# SJA1105Q_PINOUT.net
KiCad netlist of a schematic drawn in Altium Designer
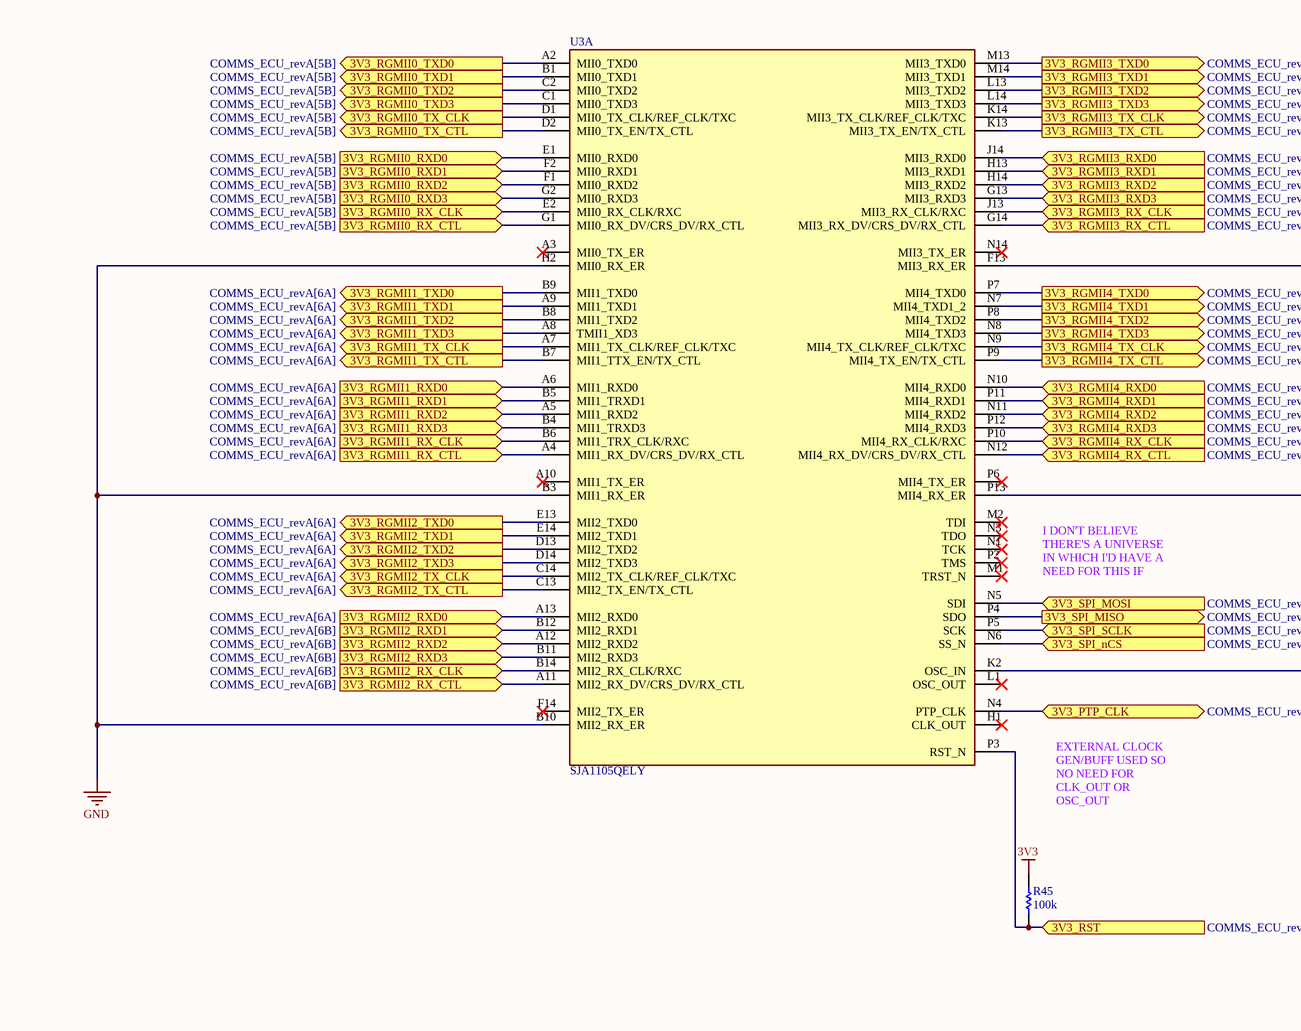
[diagram p0: SJA1105Q_PINOUT.SchDoc, top left]
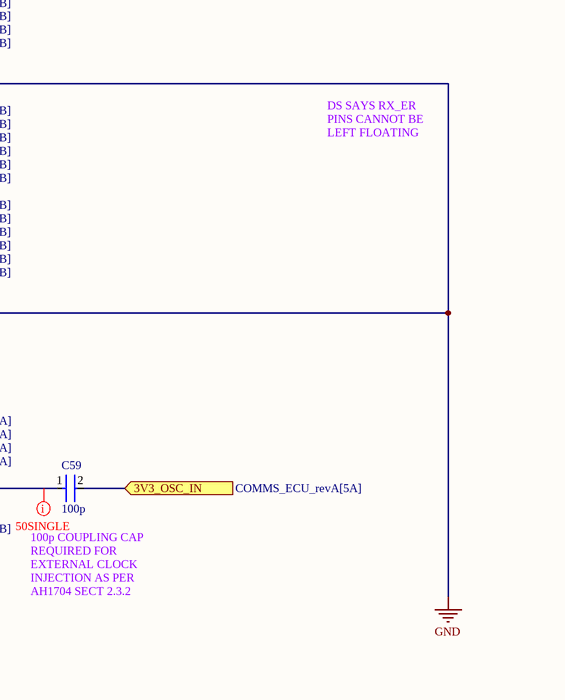
[diagram p1: SJA1105Q_PINOUT.SchDoc, top right]
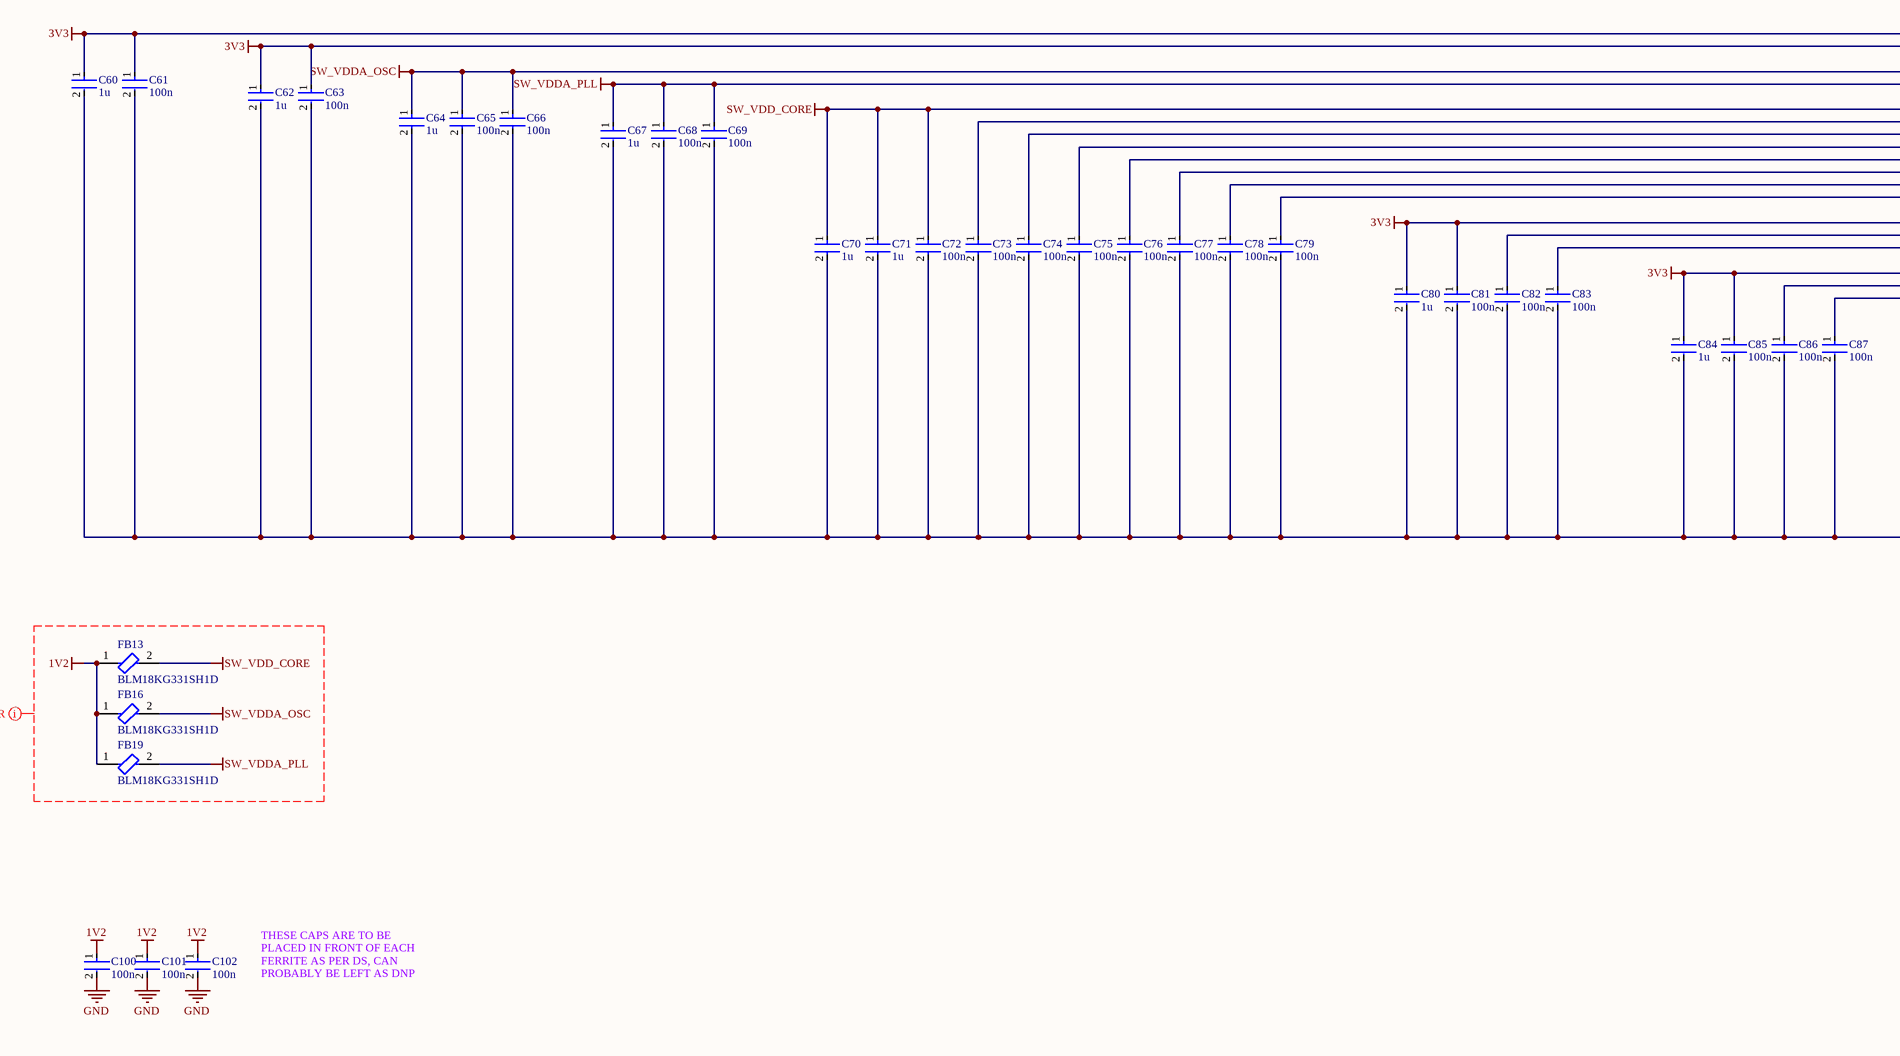
[diagram p2: SJA1105Q_PINOUT.SchDoc, bottom left]
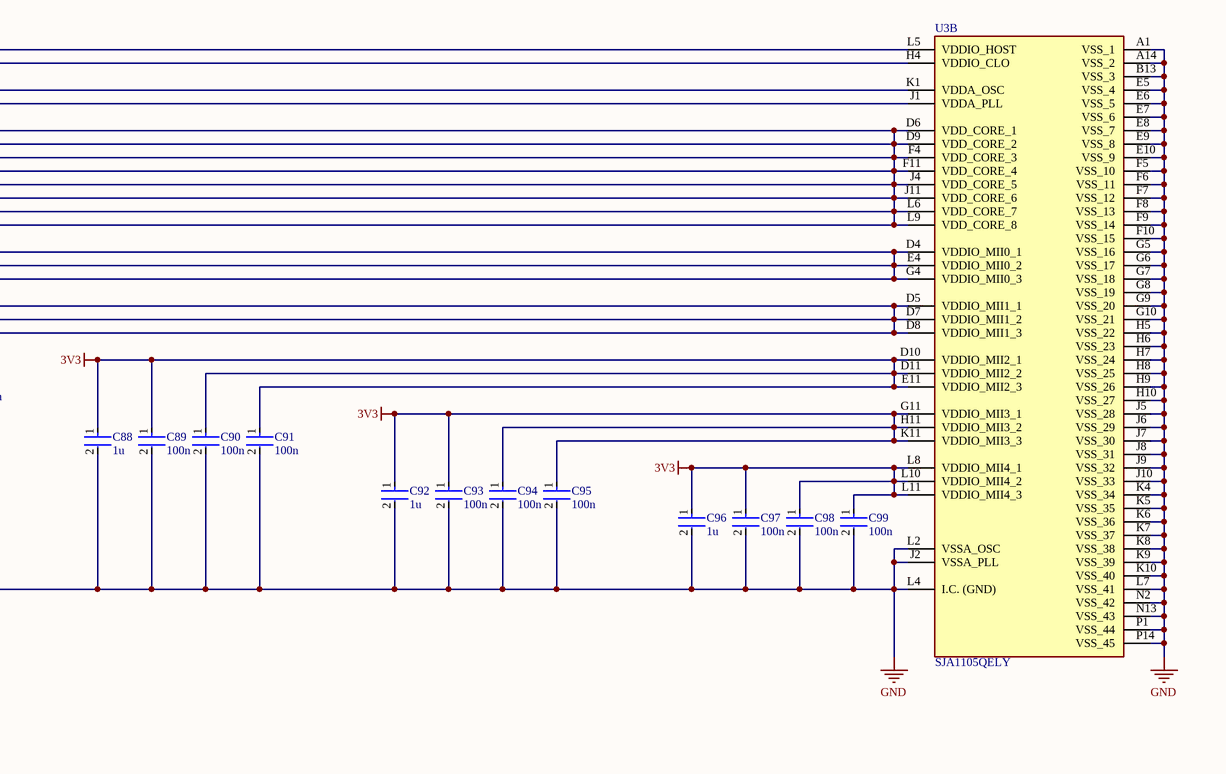
[diagram p3: SJA1105Q_PINOUT.SchDoc, bottom right]

(export (version "E")
  (design (tool "Eeschema 10.0.6"))
  (components
    (comp (ref "C59")
      (value "100p")
      (footprint "FP-0402-L_1_0_0_05-W_0_5-IPC_A")
      (description "LARGE PADS, 0402 CAP, CHANGE COMMENT TO MATCH REAL P/N")
      (libsource (lib "Space Concordia") (part "b4654b650e69147ec39a6b967a45e02"))
    )
    (comp (ref "C60")
      (value "1u")
      (footprint "FP-0402-L_1_0_0_05-W_0_5-IPC_A")
      (description "LARGE PADS, 0402 CAP, CHANGE COMMENT TO MATCH REAL P/N")
      (libsource (lib "Space Concordia") (part "b4654b650e69147ec39a6b967a45e02"))
    )
    (comp (ref "C61")
      (value "100n")
      (footprint "FP-0402-L_1_0_0_05-W_0_5-IPC_A")
      (description "LARGE PADS, 0402 CAP, CHANGE COMMENT TO MATCH REAL P/N")
      (libsource (lib "Space Concordia") (part "b4654b650e69147ec39a6b967a45e02"))
    )
    (comp (ref "C62")
      (value "1u")
      (footprint "FP-0402-L_1_0_0_05-W_0_5-IPC_A")
      (description "LARGE PADS, 0402 CAP, CHANGE COMMENT TO MATCH REAL P/N")
      (libsource (lib "Space Concordia") (part "b4654b650e69147ec39a6b967a45e02"))
    )
    (comp (ref "C63")
      (value "100n")
      (footprint "FP-0402-L_1_0_0_05-W_0_5-IPC_A")
      (description "LARGE PADS, 0402 CAP, CHANGE COMMENT TO MATCH REAL P/N")
      (libsource (lib "Space Concordia") (part "b4654b650e69147ec39a6b967a45e02"))
    )
    (comp (ref "C64")
      (value "1u")
      (footprint "FP-0402-L_1_0_0_05-W_0_5-IPC_A")
      (description "LARGE PADS, 0402 CAP, CHANGE COMMENT TO MATCH REAL P/N")
      (libsource (lib "Space Concordia") (part "b4654b650e69147ec39a6b967a45e02"))
    )
    (comp (ref "C65")
      (value "100n")
      (footprint "FP-0402-L_1_0_0_05-W_0_5-IPC_A")
      (description "LARGE PADS, 0402 CAP, CHANGE COMMENT TO MATCH REAL P/N")
      (libsource (lib "Space Concordia") (part "b4654b650e69147ec39a6b967a45e02"))
    )
    (comp (ref "C66")
      (value "100n")
      (footprint "FP-0402-L_1_0_0_05-W_0_5-IPC_A")
      (description "LARGE PADS, 0402 CAP, CHANGE COMMENT TO MATCH REAL P/N")
      (libsource (lib "Space Concordia") (part "b4654b650e69147ec39a6b967a45e02"))
    )
    (comp (ref "C67")
      (value "1u")
      (footprint "FP-0402-L_1_0_0_05-W_0_5-IPC_A")
      (description "LARGE PADS, 0402 CAP, CHANGE COMMENT TO MATCH REAL P/N")
      (libsource (lib "Space Concordia") (part "b4654b650e69147ec39a6b967a45e02"))
    )
    (comp (ref "C68")
      (value "100n")
      (footprint "FP-0402-L_1_0_0_05-W_0_5-IPC_A")
      (description "LARGE PADS, 0402 CAP, CHANGE COMMENT TO MATCH REAL P/N")
      (libsource (lib "Space Concordia") (part "b4654b650e69147ec39a6b967a45e02"))
    )
    (comp (ref "C69")
      (value "100n")
      (footprint "FP-0402-L_1_0_0_05-W_0_5-IPC_A")
      (description "LARGE PADS, 0402 CAP, CHANGE COMMENT TO MATCH REAL P/N")
      (libsource (lib "Space Concordia") (part "b4654b650e69147ec39a6b967a45e02"))
    )
    (comp (ref "C70")
      (value "1u")
      (footprint "FP-0402-L_1_0_0_05-W_0_5-IPC_A")
      (description "LARGE PADS, 0402 CAP, CHANGE COMMENT TO MATCH REAL P/N")
      (libsource (lib "Space Concordia") (part "b4654b650e69147ec39a6b967a45e02"))
    )
    (comp (ref "C71")
      (value "1u")
      (footprint "FP-0402-L_1_0_0_05-W_0_5-IPC_A")
      (description "LARGE PADS, 0402 CAP, CHANGE COMMENT TO MATCH REAL P/N")
      (libsource (lib "Space Concordia") (part "b4654b650e69147ec39a6b967a45e02"))
    )
    (comp (ref "C72")
      (value "100n")
      (footprint "FP-0402-L_1_0_0_05-W_0_5-IPC_A")
      (description "LARGE PADS, 0402 CAP, CHANGE COMMENT TO MATCH REAL P/N")
      (libsource (lib "Space Concordia") (part "b4654b650e69147ec39a6b967a45e02"))
    )
    (comp (ref "C73")
      (value "100n")
      (footprint "FP-0402-L_1_0_0_05-W_0_5-IPC_A")
      (description "LARGE PADS, 0402 CAP, CHANGE COMMENT TO MATCH REAL P/N")
      (libsource (lib "Space Concordia") (part "b4654b650e69147ec39a6b967a45e02"))
    )
    (comp (ref "C74")
      (value "100n")
      (footprint "FP-0402-L_1_0_0_05-W_0_5-IPC_A")
      (description "LARGE PADS, 0402 CAP, CHANGE COMMENT TO MATCH REAL P/N")
      (libsource (lib "Space Concordia") (part "b4654b650e69147ec39a6b967a45e02"))
    )
    (comp (ref "C75")
      (value "100n")
      (footprint "FP-0402-L_1_0_0_05-W_0_5-IPC_A")
      (description "LARGE PADS, 0402 CAP, CHANGE COMMENT TO MATCH REAL P/N")
      (libsource (lib "Space Concordia") (part "b4654b650e69147ec39a6b967a45e02"))
    )
    (comp (ref "C76")
      (value "100n")
      (footprint "FP-0402-L_1_0_0_05-W_0_5-IPC_A")
      (description "LARGE PADS, 0402 CAP, CHANGE COMMENT TO MATCH REAL P/N")
      (libsource (lib "Space Concordia") (part "b4654b650e69147ec39a6b967a45e02"))
    )
    (comp (ref "C77")
      (value "100n")
      (footprint "FP-0402-L_1_0_0_05-W_0_5-IPC_A")
      (description "LARGE PADS, 0402 CAP, CHANGE COMMENT TO MATCH REAL P/N")
      (libsource (lib "Space Concordia") (part "b4654b650e69147ec39a6b967a45e02"))
    )
    (comp (ref "C78")
      (value "100n")
      (footprint "FP-0402-L_1_0_0_05-W_0_5-IPC_A")
      (description "LARGE PADS, 0402 CAP, CHANGE COMMENT TO MATCH REAL P/N")
      (libsource (lib "Space Concordia") (part "b4654b650e69147ec39a6b967a45e02"))
    )
    (comp (ref "C79")
      (value "100n")
      (footprint "FP-0402-L_1_0_0_05-W_0_5-IPC_A")
      (description "LARGE PADS, 0402 CAP, CHANGE COMMENT TO MATCH REAL P/N")
      (libsource (lib "Space Concordia") (part "b4654b650e69147ec39a6b967a45e02"))
    )
    (comp (ref "C80")
      (value "1u")
      (footprint "FP-0402-L_1_0_0_05-W_0_5-IPC_A")
      (description "LARGE PADS, 0402 CAP, CHANGE COMMENT TO MATCH REAL P/N")
      (libsource (lib "Space Concordia") (part "b4654b650e69147ec39a6b967a45e02"))
    )
    (comp (ref "C81")
      (value "100n")
      (footprint "FP-0402-L_1_0_0_05-W_0_5-IPC_A")
      (description "LARGE PADS, 0402 CAP, CHANGE COMMENT TO MATCH REAL P/N")
      (libsource (lib "Space Concordia") (part "b4654b650e69147ec39a6b967a45e02"))
    )
    (comp (ref "C82")
      (value "100n")
      (footprint "FP-0402-L_1_0_0_05-W_0_5-IPC_A")
      (description "LARGE PADS, 0402 CAP, CHANGE COMMENT TO MATCH REAL P/N")
      (libsource (lib "Space Concordia") (part "b4654b650e69147ec39a6b967a45e02"))
    )
    (comp (ref "C83")
      (value "100n")
      (footprint "FP-0402-L_1_0_0_05-W_0_5-IPC_A")
      (description "LARGE PADS, 0402 CAP, CHANGE COMMENT TO MATCH REAL P/N")
      (libsource (lib "Space Concordia") (part "b4654b650e69147ec39a6b967a45e02"))
    )
    (comp (ref "C84")
      (value "1u")
      (footprint "FP-0402-L_1_0_0_05-W_0_5-IPC_A")
      (description "LARGE PADS, 0402 CAP, CHANGE COMMENT TO MATCH REAL P/N")
      (libsource (lib "Space Concordia") (part "b4654b650e69147ec39a6b967a45e02"))
    )
    (comp (ref "C85")
      (value "100n")
      (footprint "FP-0402-L_1_0_0_05-W_0_5-IPC_A")
      (description "LARGE PADS, 0402 CAP, CHANGE COMMENT TO MATCH REAL P/N")
      (libsource (lib "Space Concordia") (part "b4654b650e69147ec39a6b967a45e02"))
    )
    (comp (ref "C86")
      (value "100n")
      (footprint "FP-0402-L_1_0_0_05-W_0_5-IPC_A")
      (description "LARGE PADS, 0402 CAP, CHANGE COMMENT TO MATCH REAL P/N")
      (libsource (lib "Space Concordia") (part "b4654b650e69147ec39a6b967a45e02"))
    )
    (comp (ref "C87")
      (value "100n")
      (footprint "FP-0402-L_1_0_0_05-W_0_5-IPC_A")
      (description "LARGE PADS, 0402 CAP, CHANGE COMMENT TO MATCH REAL P/N")
      (libsource (lib "Space Concordia") (part "b4654b650e69147ec39a6b967a45e02"))
    )
    (comp (ref "C88")
      (value "1u")
      (footprint "FP-0402-L_1_0_0_05-W_0_5-IPC_A")
      (description "LARGE PADS, 0402 CAP, CHANGE COMMENT TO MATCH REAL P/N")
      (libsource (lib "Space Concordia") (part "b4654b650e69147ec39a6b967a45e02"))
    )
    (comp (ref "C89")
      (value "100n")
      (footprint "FP-0402-L_1_0_0_05-W_0_5-IPC_A")
      (description "LARGE PADS, 0402 CAP, CHANGE COMMENT TO MATCH REAL P/N")
      (libsource (lib "Space Concordia") (part "b4654b650e69147ec39a6b967a45e02"))
    )
    (comp (ref "C90")
      (value "100n")
      (footprint "FP-0402-L_1_0_0_05-W_0_5-IPC_A")
      (description "LARGE PADS, 0402 CAP, CHANGE COMMENT TO MATCH REAL P/N")
      (libsource (lib "Space Concordia") (part "b4654b650e69147ec39a6b967a45e02"))
    )
    (comp (ref "C91")
      (value "100n")
      (footprint "FP-0402-L_1_0_0_05-W_0_5-IPC_A")
      (description "LARGE PADS, 0402 CAP, CHANGE COMMENT TO MATCH REAL P/N")
      (libsource (lib "Space Concordia") (part "b4654b650e69147ec39a6b967a45e02"))
    )
    (comp (ref "C92")
      (value "1u")
      (footprint "FP-0402-L_1_0_0_05-W_0_5-IPC_A")
      (description "LARGE PADS, 0402 CAP, CHANGE COMMENT TO MATCH REAL P/N")
      (libsource (lib "Space Concordia") (part "b4654b650e69147ec39a6b967a45e02"))
    )
    (comp (ref "C93")
      (value "100n")
      (footprint "FP-0402-L_1_0_0_05-W_0_5-IPC_A")
      (description "LARGE PADS, 0402 CAP, CHANGE COMMENT TO MATCH REAL P/N")
      (libsource (lib "Space Concordia") (part "b4654b650e69147ec39a6b967a45e02"))
    )
    (comp (ref "C94")
      (value "100n")
      (footprint "FP-0402-L_1_0_0_05-W_0_5-IPC_A")
      (description "LARGE PADS, 0402 CAP, CHANGE COMMENT TO MATCH REAL P/N")
      (libsource (lib "Space Concordia") (part "b4654b650e69147ec39a6b967a45e02"))
    )
    (comp (ref "C95")
      (value "100n")
      (footprint "FP-0402-L_1_0_0_05-W_0_5-IPC_A")
      (description "LARGE PADS, 0402 CAP, CHANGE COMMENT TO MATCH REAL P/N")
      (libsource (lib "Space Concordia") (part "b4654b650e69147ec39a6b967a45e02"))
    )
    (comp (ref "C96")
      (value "1u")
      (footprint "FP-0402-L_1_0_0_05-W_0_5-IPC_A")
      (description "LARGE PADS, 0402 CAP, CHANGE COMMENT TO MATCH REAL P/N")
      (libsource (lib "Space Concordia") (part "b4654b650e69147ec39a6b967a45e02"))
    )
    (comp (ref "C97")
      (value "100n")
      (footprint "FP-0402-L_1_0_0_05-W_0_5-IPC_A")
      (description "LARGE PADS, 0402 CAP, CHANGE COMMENT TO MATCH REAL P/N")
      (libsource (lib "Space Concordia") (part "b4654b650e69147ec39a6b967a45e02"))
    )
    (comp (ref "C98")
      (value "100n")
      (footprint "FP-0402-L_1_0_0_05-W_0_5-IPC_A")
      (description "LARGE PADS, 0402 CAP, CHANGE COMMENT TO MATCH REAL P/N")
      (libsource (lib "Space Concordia") (part "b4654b650e69147ec39a6b967a45e02"))
    )
    (comp (ref "C99")
      (value "100n")
      (footprint "FP-0402-L_1_0_0_05-W_0_5-IPC_A")
      (description "LARGE PADS, 0402 CAP, CHANGE COMMENT TO MATCH REAL P/N")
      (libsource (lib "Space Concordia") (part "b4654b650e69147ec39a6b967a45e02"))
    )
    (comp (ref "C100")
      (value "100n")
      (footprint "FP-0402-L_1_0_0_05-W_0_5-IPC_A")
      (description "LARGE PADS, 0402 CAP, CHANGE COMMENT TO MATCH REAL P/N")
      (libsource (lib "Space Concordia") (part "b4654b650e69147ec39a6b967a45e02"))
    )
    (comp (ref "C101")
      (value "100n")
      (footprint "FP-0402-L_1_0_0_05-W_0_5-IPC_A")
      (description "LARGE PADS, 0402 CAP, CHANGE COMMENT TO MATCH REAL P/N")
      (libsource (lib "Space Concordia") (part "b4654b650e69147ec39a6b967a45e02"))
    )
    (comp (ref "C102")
      (value "100n")
      (footprint "FP-0402-L_1_0_0_05-W_0_5-IPC_A")
      (description "LARGE PADS, 0402 CAP, CHANGE COMMENT TO MATCH REAL P/N")
      (libsource (lib "Space Concordia") (part "b4654b650e69147ec39a6b967a45e02"))
    )
    (comp (ref "FB13")
      (value "BLM18KG331SH1D")
      (footprint "FP-BLM18-0_15-t0_8-IPC_B")
      (description "Chip Ferrite Bead, 0603, 330Ω @ 100MHz, 0.08Ω, 25%, 1.7A")
      (libsource (lib "Altium Content Vault") (part "5f30dd21d616792df468990f7003faa"))
    )
    (comp (ref "FB16")
      (value "BLM18KG331SH1D")
      (footprint "FP-BLM18-0_15-t0_8-IPC_B")
      (description "Chip Ferrite Bead, 0603, 330Ω @ 100MHz, 0.08Ω, 25%, 1.7A")
      (libsource (lib "Altium Content Vault") (part "5f30dd21d616792df468990f7003faa"))
    )
    (comp (ref "FB19")
      (value "BLM18KG331SH1D")
      (footprint "FP-BLM18-0_15-t0_8-IPC_B")
      (description "Chip Ferrite Bead, 0603, 330Ω @ 100MHz, 0.08Ω, 25%, 1.7A")
      (libsource (lib "Altium Content Vault") (part "5f30dd21d616792df468990f7003faa"))
    )
    (comp (ref "R45")
      (value "100k")
      (footprint "R0603B")
      (description "Resistor")
      (libsource (lib "Space Concordia") (part "Resistor"))
    )
    (comp (ref "U3")
      (value "SJA1105QELY")
      (footprint "SJA1105QELY-Footprint-1")
      (description "Ethernet Controller, Ethernet Switch, IEEE 802.3, 1.2 V, LFBGA, 159 Pins")
      (libsource (lib "Space Concordia") (part "SJA1105QELY"))
    )
  )
  (nets
    (net (code "1") (name "/3V3_OSC_IN") (class "Default")
      (node (ref "C59") (pin "2") (pinfunction "2_2") (pintype "passive"))
    )
    (net (code "2") (name "/3V3_PTP_CLK") (class "Default")
      (node (ref "U3") (pin "N4") (pinfunction "PTP_CLK_N4") (pintype "passive"))
    )
    (net (code "3") (name "/3V3_RGMII0_RXD0") (class "Default")
      (node (ref "U3") (pin "E1") (pinfunction "MII0_RXD0_E1") (pintype "passive"))
    )
    (net (code "4") (name "/3V3_RGMII0_RXD1") (class "Default")
      (node (ref "U3") (pin "F2") (pinfunction "MII0_RXD1_F2") (pintype "passive"))
    )
    (net (code "5") (name "/3V3_RGMII0_RXD2") (class "Default")
      (node (ref "U3") (pin "F1") (pinfunction "MII0_RXD2_F1") (pintype "passive"))
    )
    (net (code "6") (name "/3V3_RGMII0_RXD3") (class "Default")
      (node (ref "U3") (pin "G2") (pinfunction "MII0_RXD3_G2") (pintype "passive"))
    )
    (net (code "7") (name "/3V3_RGMII0_RX_CLK") (class "Default")
      (node (ref "U3") (pin "E2") (pinfunction "MII0_RX_CLK/RXC_E2") (pintype "passive"))
    )
    (net (code "8") (name "/3V3_RGMII0_RX_CTL") (class "Default")
      (node (ref "U3") (pin "G1") (pinfunction "MII0_RX_DV/CRS_DV/RX_CTL_G1") (pintype "passive"))
    )
    (net (code "9") (name "/3V3_RGMII0_TXD0") (class "Default")
      (node (ref "U3") (pin "A2") (pinfunction "MII0_TXD0_A2") (pintype "passive"))
    )
    (net (code "10") (name "/3V3_RGMII0_TXD1") (class "Default")
      (node (ref "U3") (pin "B1") (pinfunction "MII0_TXD1_B1") (pintype "passive"))
    )
    (net (code "11") (name "/3V3_RGMII0_TXD2") (class "Default")
      (node (ref "U3") (pin "C2") (pinfunction "MII0_TXD2_C2") (pintype "passive"))
    )
    (net (code "12") (name "/3V3_RGMII0_TXD3") (class "Default")
      (node (ref "U3") (pin "C1") (pinfunction "MII0_TXD3_C1") (pintype "passive"))
    )
    (net (code "13") (name "/3V3_RGMII0_TX_CLK") (class "Default")
      (node (ref "U3") (pin "D1") (pinfunction "MII0_TX_CLK/REF_CLK/TXC_D1") (pintype "passive"))
    )
    (net (code "14") (name "/3V3_RGMII0_TX_CTL") (class "Default")
      (node (ref "U3") (pin "D2") (pinfunction "MII0_TX_EN/TX_CTL_D2") (pintype "passive"))
    )
    (net (code "15") (name "/3V3_RGMII1_RXD0") (class "Default")
      (node (ref "U3") (pin "A6") (pinfunction "MII1_RXD0_A6") (pintype "passive"))
    )
    (net (code "16") (name "/3V3_RGMII1_RXD1") (class "Default")
      (node (ref "U3") (pin "B5") (pinfunction "MII1_TRXD1_B5") (pintype "passive"))
    )
    (net (code "17") (name "/3V3_RGMII1_RXD2") (class "Default")
      (node (ref "U3") (pin "A5") (pinfunction "MII1_RXD2_A5") (pintype "passive"))
    )
    (net (code "18") (name "/3V3_RGMII1_RXD3") (class "Default")
      (node (ref "U3") (pin "B4") (pinfunction "MII1_TRXD3_B4") (pintype "passive"))
    )
    (net (code "19") (name "/3V3_RGMII1_RX_CLK") (class "Default")
      (node (ref "U3") (pin "B6") (pinfunction "MII1_TRX_CLK/RXC_B6") (pintype "passive"))
    )
    (net (code "20") (name "/3V3_RGMII1_RX_CTL") (class "Default")
      (node (ref "U3") (pin "A4") (pinfunction "MII1_RX_DV/CRS_DV/RX_CTL_A4") (pintype "passive"))
    )
    (net (code "21") (name "/3V3_RGMII1_TXD0") (class "Default")
      (node (ref "U3") (pin "B9") (pinfunction "MII1_TXD0_B9") (pintype "passive"))
    )
    (net (code "22") (name "/3V3_RGMII1_TXD1") (class "Default")
      (node (ref "U3") (pin "A9") (pinfunction "MII1_TXD1_A9") (pintype "passive"))
    )
    (net (code "23") (name "/3V3_RGMII1_TXD2") (class "Default")
      (node (ref "U3") (pin "B8") (pinfunction "MII1_TXD2_B8") (pintype "passive"))
    )
    (net (code "24") (name "/3V3_RGMII1_TXD3") (class "Default")
      (node (ref "U3") (pin "A8") (pinfunction "TMII1_XD3_A8") (pintype "passive"))
    )
    (net (code "25") (name "/3V3_RGMII1_TX_CLK") (class "Default")
      (node (ref "U3") (pin "A7") (pinfunction "MII1_TX_CLK/REF_CLK/TXC_A7") (pintype "passive"))
    )
    (net (code "26") (name "/3V3_RGMII1_TX_CTL") (class "Default")
      (node (ref "U3") (pin "B7") (pinfunction "MII1_TTX_EN/TX_CTL_B7") (pintype "passive"))
    )
    (net (code "27") (name "/3V3_RGMII2_RXD0") (class "Default")
      (node (ref "U3") (pin "A13") (pinfunction "MII2_RXD0_A13") (pintype "passive"))
    )
    (net (code "28") (name "/3V3_RGMII2_RXD1") (class "Default")
      (node (ref "U3") (pin "B12") (pinfunction "MII2_RXD1_B12") (pintype "passive"))
    )
    (net (code "29") (name "/3V3_RGMII2_RXD2") (class "Default")
      (node (ref "U3") (pin "A12") (pinfunction "MII2_RXD2_A12") (pintype "passive"))
    )
    (net (code "30") (name "/3V3_RGMII2_RXD3") (class "Default")
      (node (ref "U3") (pin "B11") (pinfunction "MII2_RXD3_B11") (pintype "passive"))
    )
    (net (code "31") (name "/3V3_RGMII2_RX_CLK") (class "Default")
      (node (ref "U3") (pin "B14") (pinfunction "MII2_RX_CLK/RXC_B14") (pintype "passive"))
    )
    (net (code "32") (name "/3V3_RGMII2_RX_CTL") (class "Default")
      (node (ref "U3") (pin "A11") (pinfunction "MII2_RX_DV/CRS_DV/RX_CTL_A11") (pintype "passive"))
    )
    (net (code "33") (name "/3V3_RGMII2_TXD0") (class "Default")
      (node (ref "U3") (pin "E13") (pinfunction "MII2_TXD0_E13") (pintype "passive"))
    )
    (net (code "34") (name "/3V3_RGMII2_TXD1") (class "Default")
      (node (ref "U3") (pin "E14") (pinfunction "MII2_TXD1_E14") (pintype "passive"))
    )
    (net (code "35") (name "/3V3_RGMII2_TXD2") (class "Default")
      (node (ref "U3") (pin "D13") (pinfunction "MII2_TXD2_D13") (pintype "passive"))
    )
    (net (code "36") (name "/3V3_RGMII2_TXD3") (class "Default")
      (node (ref "U3") (pin "D14") (pinfunction "MII2_TXD3_D14") (pintype "passive"))
    )
    (net (code "37") (name "/3V3_RGMII2_TX_CLK") (class "Default")
      (node (ref "U3") (pin "C14") (pinfunction "MII2_TX_CLK/REF_CLK/TXC_C14") (pintype "passive"))
    )
    (net (code "38") (name "/3V3_RGMII2_TX_CTL") (class "Default")
      (node (ref "U3") (pin "C13") (pinfunction "MII2_TX_EN/TX_CTL_C13") (pintype "passive"))
    )
    (net (code "39") (name "/3V3_RGMII3_RXD0") (class "Default")
      (node (ref "U3") (pin "J14") (pinfunction "MII3_RXD0_J14") (pintype "passive"))
    )
    (net (code "40") (name "/3V3_RGMII3_RXD1") (class "Default")
      (node (ref "U3") (pin "H13") (pinfunction "MII3_RXD1_H13") (pintype "passive"))
    )
    (net (code "41") (name "/3V3_RGMII3_RXD2") (class "Default")
      (node (ref "U3") (pin "H14") (pinfunction "MII3_RXD2_H14") (pintype "passive"))
    )
    (net (code "42") (name "/3V3_RGMII3_RXD3") (class "Default")
      (node (ref "U3") (pin "G13") (pinfunction "MII3_RXD3_G13") (pintype "passive"))
    )
    (net (code "43") (name "/3V3_RGMII3_RX_CLK") (class "Default")
      (node (ref "U3") (pin "J13") (pinfunction "MII3_RX_CLK/RXC_J13") (pintype "passive"))
    )
    (net (code "44") (name "/3V3_RGMII3_RX_CTL") (class "Default")
      (node (ref "U3") (pin "G14") (pinfunction "MII3_RX_DV/CRS_DV/RX_CTL_G14") (pintype "passive"))
    )
    (net (code "45") (name "/3V3_RGMII3_TXD0") (class "Default")
      (node (ref "U3") (pin "M13") (pinfunction "MII3_TXD0_M13") (pintype "passive"))
    )
    (net (code "46") (name "/3V3_RGMII3_TXD1") (class "Default")
      (node (ref "U3") (pin "M14") (pinfunction "MII3_TXD1_M14") (pintype "passive"))
    )
    (net (code "47") (name "/3V3_RGMII3_TXD2") (class "Default")
      (node (ref "U3") (pin "L13") (pinfunction "MII3_TXD2_L13") (pintype "passive"))
    )
    (net (code "48") (name "/3V3_RGMII3_TXD3") (class "Default")
      (node (ref "U3") (pin "L14") (pinfunction "MII3_TXD3_L14") (pintype "passive"))
    )
    (net (code "49") (name "/3V3_RGMII3_TX_CLK") (class "Default")
      (node (ref "U3") (pin "K14") (pinfunction "MII3_TX_CLK/REF_CLK/TXC_K14") (pintype "passive"))
    )
    (net (code "50") (name "/3V3_RGMII3_TX_CTL") (class "Default")
      (node (ref "U3") (pin "K13") (pinfunction "MII3_TX_EN/TX_CTL_K13") (pintype "passive"))
    )
    (net (code "51") (name "/3V3_RGMII4_RXD0") (class "Default")
      (node (ref "U3") (pin "N10") (pinfunction "MII4_RXD0_N10") (pintype "passive"))
    )
    (net (code "52") (name "/3V3_RGMII4_RXD1") (class "Default")
      (node (ref "U3") (pin "P11") (pinfunction "MII4_RXD1_P11") (pintype "passive"))
    )
    (net (code "53") (name "/3V3_RGMII4_RXD2") (class "Default")
      (node (ref "U3") (pin "N11") (pinfunction "MII4_RXD2_N11") (pintype "passive"))
    )
    (net (code "54") (name "/3V3_RGMII4_RXD3") (class "Default")
      (node (ref "U3") (pin "P12") (pinfunction "MII4_RXD3_P12") (pintype "passive"))
    )
    (net (code "55") (name "/3V3_RGMII4_RX_CLK") (class "Default")
      (node (ref "U3") (pin "P10") (pinfunction "MII4_RX_CLK/RXC_P10") (pintype "passive"))
    )
    (net (code "56") (name "/3V3_RGMII4_RX_CTL") (class "Default")
      (node (ref "U3") (pin "N12") (pinfunction "MII4_RX_DV/CRS_DV/RX_CTL_N12") (pintype "passive"))
    )
    (net (code "57") (name "/3V3_RGMII4_TXD0") (class "Default")
      (node (ref "U3") (pin "P7") (pinfunction "MII4_TXD0_P7") (pintype "passive"))
    )
    (net (code "58") (name "/3V3_RGMII4_TXD1") (class "Default")
      (node (ref "U3") (pin "N7") (pinfunction "MII4_TXD1_2_N7") (pintype "passive"))
    )
    (net (code "59") (name "/3V3_RGMII4_TXD2") (class "Default")
      (node (ref "U3") (pin "P8") (pinfunction "MII4_TXD2_P8") (pintype "passive"))
    )
    (net (code "60") (name "/3V3_RGMII4_TXD3") (class "Default")
      (node (ref "U3") (pin "N8") (pinfunction "MII4_TXD3_N8") (pintype "passive"))
    )
    (net (code "61") (name "/3V3_RGMII4_TX_CLK") (class "Default")
      (node (ref "U3") (pin "N9") (pinfunction "MII4_TX_CLK/REF_CLK/TXC_N9") (pintype "passive"))
    )
    (net (code "62") (name "/3V3_RGMII4_TX_CTL") (class "Default")
      (node (ref "U3") (pin "P9") (pinfunction "MII4_TX_EN/TX_CTL_P9") (pintype "passive"))
    )
    (net (code "63") (name "/3V3_RST") (class "Default")
      (node (ref "R45") (pin "1") (pinfunction "1_1") (pintype "passive"))
      (node (ref "U3") (pin "P3") (pinfunction "RST_N_P3") (pintype "passive"))
    )
    (net (code "64") (name "/3V3_SPI_MISO") (class "Default")
      (node (ref "U3") (pin "P4") (pinfunction "SDO_P4") (pintype "passive"))
    )
    (net (code "65") (name "/3V3_SPI_MOSI") (class "Default")
      (node (ref "U3") (pin "N5") (pinfunction "SDI_N5") (pintype "passive"))
    )
    (net (code "66") (name "/3V3_SPI_SCLK") (class "Default")
      (node (ref "U3") (pin "P5") (pinfunction "SCK_P5") (pintype "passive"))
    )
    (net (code "67") (name "/3V3_SPI_nCS") (class "Default")
      (node (ref "U3") (pin "N6") (pinfunction "SS_N_N6") (pintype "passive"))
    )
    (net (code "68") (name "1V2") (class "Default")
      (node (ref "C100") (pin "1") (pinfunction "1_1") (pintype "passive"))
      (node (ref "C101") (pin "1") (pinfunction "1_1") (pintype "passive"))
      (node (ref "C102") (pin "1") (pinfunction "1_1") (pintype "passive"))
      (node (ref "FB13") (pin "1") (pinfunction "1_1") (pintype "passive"))
      (node (ref "FB16") (pin "1") (pinfunction "1_1") (pintype "passive"))
      (node (ref "FB19") (pin "1") (pinfunction "1_1") (pintype "passive"))
    )
    (net (code "69") (name "3V3") (class "Default")
      (node (ref "C60") (pin "1") (pinfunction "1_1") (pintype "passive"))
      (node (ref "C61") (pin "1") (pinfunction "1_1") (pintype "passive"))
      (node (ref "C62") (pin "1") (pinfunction "1_1") (pintype "passive"))
      (node (ref "C63") (pin "1") (pinfunction "1_1") (pintype "passive"))
      (node (ref "C80") (pin "1") (pinfunction "1_1") (pintype "passive"))
      (node (ref "C81") (pin "1") (pinfunction "1_1") (pintype "passive"))
      (node (ref "C82") (pin "1") (pinfunction "1_1") (pintype "passive"))
      (node (ref "C83") (pin "1") (pinfunction "1_1") (pintype "passive"))
      (node (ref "C84") (pin "1") (pinfunction "1_1") (pintype "passive"))
      (node (ref "C85") (pin "1") (pinfunction "1_1") (pintype "passive"))
      (node (ref "C86") (pin "1") (pinfunction "1_1") (pintype "passive"))
      (node (ref "C87") (pin "1") (pinfunction "1_1") (pintype "passive"))
      (node (ref "C88") (pin "1") (pinfunction "1_1") (pintype "passive"))
      (node (ref "C89") (pin "1") (pinfunction "1_1") (pintype "passive"))
      (node (ref "C90") (pin "1") (pinfunction "1_1") (pintype "passive"))
      (node (ref "C91") (pin "1") (pinfunction "1_1") (pintype "passive"))
      (node (ref "C92") (pin "1") (pinfunction "1_1") (pintype "passive"))
      (node (ref "C93") (pin "1") (pinfunction "1_1") (pintype "passive"))
      (node (ref "C94") (pin "1") (pinfunction "1_1") (pintype "passive"))
      (node (ref "C95") (pin "1") (pinfunction "1_1") (pintype "passive"))
      (node (ref "C96") (pin "1") (pinfunction "1_1") (pintype "passive"))
      (node (ref "C97") (pin "1") (pinfunction "1_1") (pintype "passive"))
      (node (ref "C98") (pin "1") (pinfunction "1_1") (pintype "passive"))
      (node (ref "C99") (pin "1") (pinfunction "1_1") (pintype "passive"))
      (node (ref "R45") (pin "2") (pinfunction "2_2") (pintype "passive"))
      (node (ref "U3") (pin "D10") (pinfunction "VDDIO_MII2_1_D10") (pintype "passive"))
      (node (ref "U3") (pin "D11") (pinfunction "VDDIO_MII2_2_D11") (pintype "passive"))
      (node (ref "U3") (pin "D4") (pinfunction "VDDIO_MII0_1_D4") (pintype "passive"))
      (node (ref "U3") (pin "D5") (pinfunction "VDDIO_MII1_1_D5") (pintype "passive"))
      (node (ref "U3") (pin "D7") (pinfunction "VDDIO_MII1_2_D7") (pintype "passive"))
      (node (ref "U3") (pin "D8") (pinfunction "VDDIO_MII1_3_D8") (pintype "passive"))
      (node (ref "U3") (pin "E11") (pinfunction "VDDIO_MII2_3_E11") (pintype "passive"))
      (node (ref "U3") (pin "E4") (pinfunction "VDDIO_MII0_2_E4") (pintype "passive"))
      (node (ref "U3") (pin "G11") (pinfunction "VDDIO_MII3_1_G11") (pintype "passive"))
      (node (ref "U3") (pin "G4") (pinfunction "VDDIO_MII0_3_G4") (pintype "passive"))
      (node (ref "U3") (pin "H11") (pinfunction "VDDIO_MII3_2_H11") (pintype "passive"))
      (node (ref "U3") (pin "H4") (pinfunction "VDDIO_CLO_H4") (pintype "passive"))
      (node (ref "U3") (pin "K11") (pinfunction "VDDIO_MII3_3_K11") (pintype "passive"))
      (node (ref "U3") (pin "L10") (pinfunction "VDDIO_MII4_2_L10") (pintype "passive"))
      (node (ref "U3") (pin "L11") (pinfunction "VDDIO_MII4_3_L11") (pintype "passive"))
      (node (ref "U3") (pin "L5") (pinfunction "VDDIO_HOST_L5") (pintype "passive"))
      (node (ref "U3") (pin "L8") (pinfunction "VDDIO_MII4_1_L8") (pintype "passive"))
    )
    (net (code "70") (name "GND") (class "Default")
      (node (ref "C100") (pin "2") (pinfunction "2_2") (pintype "passive"))
      (node (ref "C101") (pin "2") (pinfunction "2_2") (pintype "passive"))
      (node (ref "C102") (pin "2") (pinfunction "2_2") (pintype "passive"))
      (node (ref "C60") (pin "2") (pinfunction "2_2") (pintype "passive"))
      (node (ref "C61") (pin "2") (pinfunction "2_2") (pintype "passive"))
      (node (ref "C62") (pin "2") (pinfunction "2_2") (pintype "passive"))
      (node (ref "C63") (pin "2") (pinfunction "2_2") (pintype "passive"))
      (node (ref "C64") (pin "2") (pinfunction "2_2") (pintype "passive"))
      (node (ref "C65") (pin "2") (pinfunction "2_2") (pintype "passive"))
      (node (ref "C66") (pin "2") (pinfunction "2_2") (pintype "passive"))
      (node (ref "C67") (pin "2") (pinfunction "2_2") (pintype "passive"))
      (node (ref "C68") (pin "2") (pinfunction "2_2") (pintype "passive"))
      (node (ref "C69") (pin "2") (pinfunction "2_2") (pintype "passive"))
      (node (ref "C70") (pin "2") (pinfunction "2_2") (pintype "passive"))
      (node (ref "C71") (pin "2") (pinfunction "2_2") (pintype "passive"))
      (node (ref "C72") (pin "2") (pinfunction "2_2") (pintype "passive"))
      (node (ref "C73") (pin "2") (pinfunction "2_2") (pintype "passive"))
      (node (ref "C74") (pin "2") (pinfunction "2_2") (pintype "passive"))
      (node (ref "C75") (pin "2") (pinfunction "2_2") (pintype "passive"))
      (node (ref "C76") (pin "2") (pinfunction "2_2") (pintype "passive"))
      (node (ref "C77") (pin "2") (pinfunction "2_2") (pintype "passive"))
      (node (ref "C78") (pin "2") (pinfunction "2_2") (pintype "passive"))
      (node (ref "C79") (pin "2") (pinfunction "2_2") (pintype "passive"))
      (node (ref "C80") (pin "2") (pinfunction "2_2") (pintype "passive"))
      (node (ref "C81") (pin "2") (pinfunction "2_2") (pintype "passive"))
      (node (ref "C82") (pin "2") (pinfunction "2_2") (pintype "passive"))
      (node (ref "C83") (pin "2") (pinfunction "2_2") (pintype "passive"))
      (node (ref "C84") (pin "2") (pinfunction "2_2") (pintype "passive"))
      (node (ref "C85") (pin "2") (pinfunction "2_2") (pintype "passive"))
      (node (ref "C86") (pin "2") (pinfunction "2_2") (pintype "passive"))
      (node (ref "C87") (pin "2") (pinfunction "2_2") (pintype "passive"))
      (node (ref "C88") (pin "2") (pinfunction "2_2") (pintype "passive"))
      (node (ref "C89") (pin "2") (pinfunction "2_2") (pintype "passive"))
      (node (ref "C90") (pin "2") (pinfunction "2_2") (pintype "passive"))
      (node (ref "C91") (pin "2") (pinfunction "2_2") (pintype "passive"))
      (node (ref "C92") (pin "2") (pinfunction "2_2") (pintype "passive"))
      (node (ref "C93") (pin "2") (pinfunction "2_2") (pintype "passive"))
      (node (ref "C94") (pin "2") (pinfunction "2_2") (pintype "passive"))
      (node (ref "C95") (pin "2") (pinfunction "2_2") (pintype "passive"))
      (node (ref "C96") (pin "2") (pinfunction "2_2") (pintype "passive"))
      (node (ref "C97") (pin "2") (pinfunction "2_2") (pintype "passive"))
      (node (ref "C98") (pin "2") (pinfunction "2_2") (pintype "passive"))
      (node (ref "C99") (pin "2") (pinfunction "2_2") (pintype "passive"))
      (node (ref "U3") (pin "A1") (pinfunction "VSS_1_A1") (pintype "passive"))
      (node (ref "U3") (pin "A14") (pinfunction "VSS_2_A14") (pintype "passive"))
      (node (ref "U3") (pin "B10") (pinfunction "MII2_RX_ER_B10") (pintype "passive"))
      (node (ref "U3") (pin "B13") (pinfunction "VSS_3_B13") (pintype "passive"))
      (node (ref "U3") (pin "B3") (pinfunction "MII1_RX_ER_B3") (pintype "passive"))
      (node (ref "U3") (pin "E10") (pinfunction "VSS_9_E10") (pintype "passive"))
      (node (ref "U3") (pin "E5") (pinfunction "VSS_4_E5") (pintype "passive"))
      (node (ref "U3") (pin "E6") (pinfunction "VSS_5_E6") (pintype "passive"))
      (node (ref "U3") (pin "E7") (pinfunction "VSS_6_E7") (pintype "passive"))
      (node (ref "U3") (pin "E8") (pinfunction "VSS_7_E8") (pintype "passive"))
      (node (ref "U3") (pin "E9") (pinfunction "VSS_8_E9") (pintype "passive"))
      (node (ref "U3") (pin "F10") (pinfunction "VSS_15_F10") (pintype "passive"))
      (node (ref "U3") (pin "F13") (pinfunction "MII3_RX_ER_F13") (pintype "passive"))
      (node (ref "U3") (pin "F5") (pinfunction "VSS_10_F5") (pintype "passive"))
      (node (ref "U3") (pin "F6") (pinfunction "VSS_11_F6") (pintype "passive"))
      (node (ref "U3") (pin "F7") (pinfunction "VSS_12_F7") (pintype "passive"))
      (node (ref "U3") (pin "F8") (pinfunction "VSS_13_F8") (pintype "passive"))
      (node (ref "U3") (pin "F9") (pinfunction "VSS_14_F9") (pintype "passive"))
      (node (ref "U3") (pin "G10") (pinfunction "VSS_21_G10") (pintype "passive"))
      (node (ref "U3") (pin "G5") (pinfunction "VSS_16_G5") (pintype "passive"))
      (node (ref "U3") (pin "G6") (pinfunction "VSS_17_G6") (pintype "passive"))
      (node (ref "U3") (pin "G7") (pinfunction "VSS_18_G7") (pintype "passive"))
      (node (ref "U3") (pin "G8") (pinfunction "VSS_19_G8") (pintype "passive"))
      (node (ref "U3") (pin "G9") (pinfunction "VSS_20_G9") (pintype "passive"))
      (node (ref "U3") (pin "H10") (pinfunction "VSS_27_H10") (pintype "passive"))
      (node (ref "U3") (pin "H2") (pinfunction "MII0_RX_ER_H2") (pintype "passive"))
      (node (ref "U3") (pin "H5") (pinfunction "VSS_22_H5") (pintype "passive"))
      (node (ref "U3") (pin "H6") (pinfunction "VSS_23_H6") (pintype "passive"))
      (node (ref "U3") (pin "H7") (pinfunction "VSS_24_H7") (pintype "passive"))
      (node (ref "U3") (pin "H8") (pinfunction "VSS_25_H8") (pintype "passive"))
      (node (ref "U3") (pin "H9") (pinfunction "VSS_26_H9") (pintype "passive"))
      (node (ref "U3") (pin "J10") (pinfunction "VSS_33_J10") (pintype "passive"))
      (node (ref "U3") (pin "J2") (pinfunction "VSSA_PLL_J2") (pintype "passive"))
      (node (ref "U3") (pin "J5") (pinfunction "VSS_28_J5") (pintype "passive"))
      (node (ref "U3") (pin "J6") (pinfunction "VSS_29_J6") (pintype "passive"))
      (node (ref "U3") (pin "J7") (pinfunction "VSS_30_J7") (pintype "passive"))
      (node (ref "U3") (pin "J8") (pinfunction "VSS_31_J8") (pintype "passive"))
      (node (ref "U3") (pin "J9") (pinfunction "VSS_32_J9") (pintype "passive"))
      (node (ref "U3") (pin "K10") (pinfunction "VSS_40_K10") (pintype "passive"))
      (node (ref "U3") (pin "K4") (pinfunction "VSS_34_K4") (pintype "passive"))
      (node (ref "U3") (pin "K5") (pinfunction "VSS_35_K5") (pintype "passive"))
      (node (ref "U3") (pin "K6") (pinfunction "VSS_36_K6") (pintype "passive"))
      (node (ref "U3") (pin "K7") (pinfunction "VSS_37_K7") (pintype "passive"))
      (node (ref "U3") (pin "K8") (pinfunction "VSS_38_K8") (pintype "passive"))
      (node (ref "U3") (pin "K9") (pinfunction "VSS_39_K9") (pintype "passive"))
      (node (ref "U3") (pin "L2") (pinfunction "VSSA_OSC_L2") (pintype "passive"))
      (node (ref "U3") (pin "L4") (pinfunction "I.C._(GND)_L4") (pintype "passive"))
      (node (ref "U3") (pin "L7") (pinfunction "VSS_41_L7") (pintype "passive"))
      (node (ref "U3") (pin "N13") (pinfunction "VSS_43_N13") (pintype "passive"))
      (node (ref "U3") (pin "N2") (pinfunction "VSS_42_N2") (pintype "passive"))
      (node (ref "U3") (pin "P1") (pinfunction "VSS_44_P1") (pintype "passive"))
      (node (ref "U3") (pin "P13") (pinfunction "MII4_RX_ER_P13") (pintype "passive"))
      (node (ref "U3") (pin "P14") (pinfunction "VSS_45_P14") (pintype "passive"))
    )
    (net (code "71") (name "Net-(U3A-OSC_IN)") (class "Default")
      (node (ref "C59") (pin "1") (pinfunction "1_1") (pintype "passive"))
      (node (ref "U3") (pin "K2") (pinfunction "OSC_IN_K2") (pintype "passive"))
    )
    (net (code "72") (name "SW_VDDA_OSC") (class "Default")
      (node (ref "C64") (pin "1") (pinfunction "1_1") (pintype "passive"))
      (node (ref "C65") (pin "1") (pinfunction "1_1") (pintype "passive"))
      (node (ref "C66") (pin "1") (pinfunction "1_1") (pintype "passive"))
      (node (ref "FB16") (pin "2") (pinfunction "2_2") (pintype "passive"))
      (node (ref "U3") (pin "K1") (pinfunction "VDDA_OSC_K1") (pintype "passive"))
    )
    (net (code "73") (name "SW_VDDA_PLL") (class "Default")
      (node (ref "C67") (pin "1") (pinfunction "1_1") (pintype "passive"))
      (node (ref "C68") (pin "1") (pinfunction "1_1") (pintype "passive"))
      (node (ref "C69") (pin "1") (pinfunction "1_1") (pintype "passive"))
      (node (ref "FB19") (pin "2") (pinfunction "2_2") (pintype "passive"))
      (node (ref "U3") (pin "J1") (pinfunction "VDDA_PLL_J1") (pintype "passive"))
    )
    (net (code "74") (name "SW_VDD_CORE") (class "Default")
      (node (ref "C70") (pin "1") (pinfunction "1_1") (pintype "passive"))
      (node (ref "C71") (pin "1") (pinfunction "1_1") (pintype "passive"))
      (node (ref "C72") (pin "1") (pinfunction "1_1") (pintype "passive"))
      (node (ref "C73") (pin "1") (pinfunction "1_1") (pintype "passive"))
      (node (ref "C74") (pin "1") (pinfunction "1_1") (pintype "passive"))
      (node (ref "C75") (pin "1") (pinfunction "1_1") (pintype "passive"))
      (node (ref "C76") (pin "1") (pinfunction "1_1") (pintype "passive"))
      (node (ref "C77") (pin "1") (pinfunction "1_1") (pintype "passive"))
      (node (ref "C78") (pin "1") (pinfunction "1_1") (pintype "passive"))
      (node (ref "C79") (pin "1") (pinfunction "1_1") (pintype "passive"))
      (node (ref "FB13") (pin "2") (pinfunction "2_2") (pintype "passive"))
      (node (ref "U3") (pin "D6") (pinfunction "VDD_CORE_1_D6") (pintype "passive"))
      (node (ref "U3") (pin "D9") (pinfunction "VDD_CORE_2_D9") (pintype "passive"))
      (node (ref "U3") (pin "F11") (pinfunction "VDD_CORE_4_F11") (pintype "passive"))
      (node (ref "U3") (pin "F4") (pinfunction "VDD_CORE_3_F4") (pintype "passive"))
      (node (ref "U3") (pin "J11") (pinfunction "VDD_CORE_6_J11") (pintype "passive"))
      (node (ref "U3") (pin "J4") (pinfunction "VDD_CORE_5_J4") (pintype "passive"))
      (node (ref "U3") (pin "L6") (pinfunction "VDD_CORE_7_L6") (pintype "passive"))
      (node (ref "U3") (pin "L9") (pinfunction "VDD_CORE_8_L9") (pintype "passive"))
    )
    (net (code "75") (name "unconnected-(U3A-CLK_OUT-PadH1)") (class "Default")
      (node (ref "U3") (pin "H1") (pinfunction "CLK_OUT_H1") (pintype "passive+no_connect"))
    )
    (net (code "76") (name "unconnected-(U3A-MII0_TX_ER-PadA3)") (class "Default")
      (node (ref "U3") (pin "A3") (pinfunction "MII0_TX_ER_A3") (pintype "passive+no_connect"))
    )
    (net (code "77") (name "unconnected-(U3A-MII1_TX_ER-PadA10)") (class "Default")
      (node (ref "U3") (pin "A10") (pinfunction "MII1_TX_ER_A10") (pintype "passive+no_connect"))
    )
    (net (code "78") (name "unconnected-(U3A-MII2_TX_ER-PadF14)") (class "Default")
      (node (ref "U3") (pin "F14") (pinfunction "MII2_TX_ER_F14") (pintype "passive+no_connect"))
    )
    (net (code "79") (name "unconnected-(U3A-MII3_TX_ER-PadN14)") (class "Default")
      (node (ref "U3") (pin "N14") (pinfunction "MII3_TX_ER_N14") (pintype "passive+no_connect"))
    )
    (net (code "80") (name "unconnected-(U3A-MII4_TX_ER-PadP6)") (class "Default")
      (node (ref "U3") (pin "P6") (pinfunction "MII4_TX_ER_P6") (pintype "passive+no_connect"))
    )
    (net (code "81") (name "unconnected-(U3A-OSC_OUT-PadL1)") (class "Default")
      (node (ref "U3") (pin "L1") (pinfunction "OSC_OUT_L1") (pintype "passive+no_connect"))
    )
    (net (code "82") (name "unconnected-(U3A-TCK-PadN1)") (class "Default")
      (node (ref "U3") (pin "N1") (pinfunction "TCK_N1") (pintype "passive+no_connect"))
    )
    (net (code "83") (name "unconnected-(U3A-TDI-PadM2)") (class "Default")
      (node (ref "U3") (pin "M2") (pinfunction "TDI_M2") (pintype "passive+no_connect"))
    )
    (net (code "84") (name "unconnected-(U3A-TDO-PadN3)") (class "Default")
      (node (ref "U3") (pin "N3") (pinfunction "TDO_N3") (pintype "passive+no_connect"))
    )
    (net (code "85") (name "unconnected-(U3A-TMS-PadP2)") (class "Default")
      (node (ref "U3") (pin "P2") (pinfunction "TMS_P2") (pintype "passive+no_connect"))
    )
    (net (code "86") (name "unconnected-(U3A-TRST_N-PadM1)") (class "Default")
      (node (ref "U3") (pin "M1") (pinfunction "TRST_N_M1") (pintype "passive+no_connect"))
    )
  )
)
